# MCU_IO.net
KiCad netlist of a schematic drawn in Altium Designer
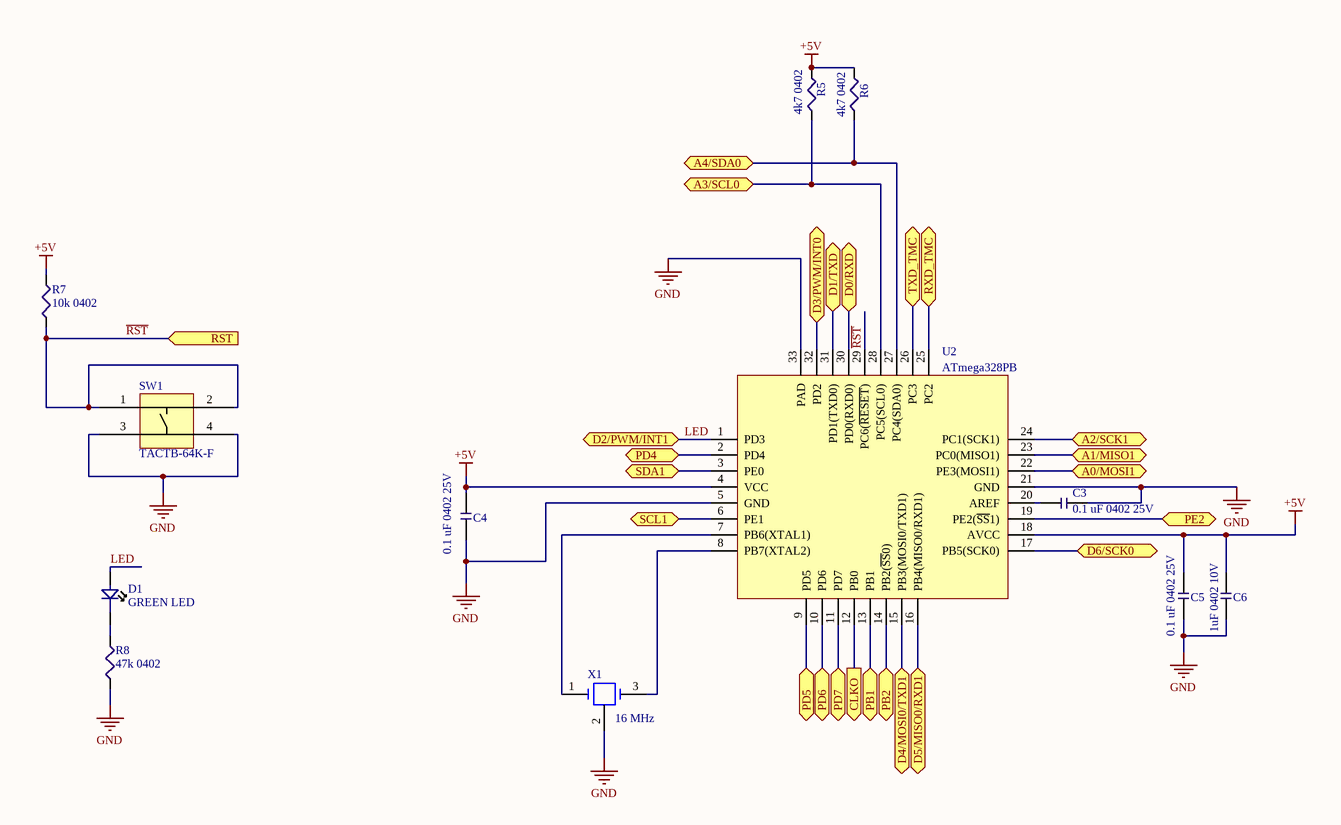
[diagram p0: MCU+IO.SchDoc]

(export (version "E")
  (design (tool "Eeschema 10.0.6"))
  (components
    (comp (ref "C3")
      (value "0.1 uF 0402 25V")
      (footprint "CAP_0402")
      (description "0.1UF 25V 10% X5R 0402")
      (fields (field (name "TOLERANCE") "10%") (field (name "VOLTAGE") "25V"))
      (libsource (lib "ON Development Vault") (part "Capacitor"))
    )
    (comp (ref "C4")
      (value "0.1 uF 0402 25V")
      (footprint "CAP_0402")
      (description "0.1UF 25V 10% X5R 0402")
      (fields (field (name "TOLERANCE") "10%") (field (name "VOLTAGE") "25V"))
      (libsource (lib "ON Development Vault") (part "Capacitor"))
    )
    (comp (ref "C5")
      (value "0.1 uF 0402 25V")
      (footprint "CAP_0402")
      (description "0.1UF 25V 10% X5R 0402")
      (fields (field (name "TOLERANCE") "10%") (field (name "VOLTAGE") "25V"))
      (libsource (lib "ON Development Vault") (part "Capacitor"))
    )
    (comp (ref "C6")
      (value "1uF 0402 10V")
      (footprint "CAP_0402")
      (description "1uF 0402 10V 10% X5R")
      (fields (field (name "TOLERANCE") "10 %") (field (name "VOLTAGE") "10 V"))
      (libsource (lib "ON Development Vault") (part "Capacitor"))
    )
    (comp (ref "D1")
      (value "GREEN LED")
      (footprint "0402 LED")
      (description "0402 SMD LED")
      (fields (field (name "MFG. PART NUMBER") "LTST-C281KGKT"))
      (libsource (lib "ON Development Vault") (part "LED"))
    )
    (comp (ref "R5")
      (value "4k7 0402")
      (footprint "RES_0402")
      (description "RES SMD 4.7K OHM 1% 1/16W 0402")
      (fields (field (name "POWER") "1/16W") (field (name "TOLERANCE") "1"))
      (libsource (lib "ON Development Vault") (part "Resistor"))
    )
    (comp (ref "R6")
      (value "4k7 0402")
      (footprint "RES_0402")
      (description "RES SMD 4.7K OHM 1% 1/16W 0402")
      (fields (field (name "POWER") "1/16W") (field (name "TOLERANCE") "1"))
      (libsource (lib "ON Development Vault") (part "Resistor"))
    )
    (comp (ref "R7")
      (value "10k 0402")
      (footprint "RES_0402")
      (description "RES SMD 10K OHM 1% 1/16W 0402")
      (fields (field (name "POWER") "1/16 W") (field (name "TOLERANCE") "1 %"))
      (libsource (lib "ON Development Vault") (part "Resistor"))
    )
    (comp (ref "R8")
      (value "47k 0402")
      (footprint "RES_0402")
      (description "RES SMD 47K OHM 1% 1/16W 0402")
      (fields (field (name "POWER") "1/16W") (field (name "TOLERANCE") "1%"))
      (libsource (lib "ON Development Vault") (part "Resistor"))
    )
    (comp (ref "SW1")
      (value "TACTB-64K-F")
      (footprint "TACTB-64K-F")
      (description "Microswitch TACT; SPST-NO; Positions:2; 0.05A/12VDC;")
      (libsource (lib "ON Development Vault") (part "CMP-013-0002-1"))
    )
    (comp (ref "U2")
      (value "ATmega328PB")
      (footprint "QFN50P500X500X90_HS-33N")
      (description "IC MCU 8BIT 32KB FLASH 32TQFP")
      (libsource (lib "ON Development Vault") (part "ATmega328PB"))
    )
    (comp (ref "X1")
      (value "16 MHz")
      (footprint "CSTCE16XTAL")
      (description "CER RES 16.0000MHZ 15PF SMD")
      (fields (field (name "MFG. PART NUMBER") "CSTCE16M0V53-R0"))
      (libsource (lib "ON Development Vault") (part "Xtal 3-pin"))
    )
  )
  (nets
    (net (code "1") (name "+5V") (class "Default")
      (node (ref "C4") (pin "1") (pinfunction "1_1") (pintype "passive"))
      (node (ref "C5") (pin "2") (pinfunction "2_2") (pintype "passive"))
      (node (ref "C6") (pin "2") (pinfunction "2_2") (pintype "passive"))
      (node (ref "R5") (pin "2") (pinfunction "2_2") (pintype "passive"))
      (node (ref "R6") (pin "2") (pinfunction "2_2") (pintype "passive"))
      (node (ref "R7") (pin "2") (pinfunction "2_2") (pintype "passive"))
      (node (ref "U2") (pin "18") (pinfunction "AVCC_18") (pintype "passive"))
      (node (ref "U2") (pin "4") (pinfunction "VCC_4") (pintype "passive"))
    )
    (net (code "2") (name "/A0{slash}MOSI1") (class "Default")
      (node (ref "U2") (pin "22") (pinfunction "PE3(MOSI1)_22") (pintype "passive"))
    )
    (net (code "3") (name "/A1{slash}MISO1") (class "Default")
      (node (ref "U2") (pin "23") (pinfunction "PC0(MISO1)_23") (pintype "passive"))
    )
    (net (code "4") (name "/A2{slash}SCK1") (class "Default")
      (node (ref "U2") (pin "24") (pinfunction "PC1(SCK1)_24") (pintype "passive"))
    )
    (net (code "5") (name "/A3{slash}SCL0") (class "Default")
      (node (ref "R5") (pin "1") (pinfunction "1_1") (pintype "passive"))
      (node (ref "U2") (pin "28") (pinfunction "PC5(SCL0)_28") (pintype "passive"))
    )
    (net (code "6") (name "/A4{slash}SDA0") (class "Default")
      (node (ref "R6") (pin "1") (pinfunction "1_1") (pintype "passive"))
      (node (ref "U2") (pin "27") (pinfunction "PC4(SDA0)_27") (pintype "passive"))
    )
    (net (code "7") (name "/CLKO") (class "Default")
      (node (ref "U2") (pin "12") (pinfunction "PB0_12") (pintype "passive"))
    )
    (net (code "8") (name "/D0{slash}RXD") (class "Default")
      (node (ref "U2") (pin "30") (pinfunction "PD0(RXD0)_30") (pintype "passive"))
    )
    (net (code "9") (name "/D1{slash}TXD") (class "Default")
      (node (ref "U2") (pin "31") (pinfunction "PD1(TXD0)_31") (pintype "passive"))
    )
    (net (code "10") (name "/D3{slash}PWM{slash}INT0") (class "Default")
      (node (ref "U2") (pin "32") (pinfunction "PD2_32") (pintype "passive"))
    )
    (net (code "11") (name "/D4{slash}MOSI0{slash}TXD1") (class "Default")
      (node (ref "U2") (pin "15") (pinfunction "PB3(MOSI0/TXD1)_15") (pintype "passive"))
    )
    (net (code "12") (name "/D5{slash}MISO0{slash}RXD1") (class "Default")
      (node (ref "U2") (pin "16") (pinfunction "PB4(MISO0/RXD1)_16") (pintype "passive"))
    )
    (net (code "13") (name "/D6{slash}SCK0") (class "Default")
      (node (ref "U2") (pin "17") (pinfunction "PB5(SCK0)_17") (pintype "passive"))
    )
    (net (code "14") (name "/LED") (class "Default")
      (node (ref "D1") (pin "1") (pinfunction "1_1") (pintype "passive"))
      (node (ref "U2") (pin "1") (pinfunction "PD3_1") (pintype "passive"))
    )
    (net (code "15") (name "/PB1") (class "Default")
      (node (ref "U2") (pin "13") (pinfunction "PB1_13") (pintype "passive"))
    )
    (net (code "16") (name "/PB2") (class "Default")
      (node (ref "U2") (pin "14") (pinfunction "PB2(~{SS}0)_14") (pintype "passive"))
    )
    (net (code "17") (name "/PD4") (class "Default")
      (node (ref "U2") (pin "2") (pinfunction "PD4_2") (pintype "passive"))
    )
    (net (code "18") (name "/PD5") (class "Default")
      (node (ref "U2") (pin "9") (pinfunction "PD5_9") (pintype "passive"))
    )
    (net (code "19") (name "/PD6") (class "Default")
      (node (ref "U2") (pin "10") (pinfunction "PD6_10") (pintype "passive"))
    )
    (net (code "20") (name "/PD7") (class "Default")
      (node (ref "U2") (pin "11") (pinfunction "PD7_11") (pintype "passive"))
    )
    (net (code "21") (name "/PE2") (class "Default")
      (node (ref "U2") (pin "19") (pinfunction "PE2(~{SS}1)_19") (pintype "passive"))
    )
    (net (code "22") (name "/RXD_TMC") (class "Default")
      (node (ref "U2") (pin "25") (pinfunction "PC2_25") (pintype "passive"))
    )
    (net (code "23") (name "/SCL1") (class "Default")
      (node (ref "U2") (pin "6") (pinfunction "PE1_6") (pintype "passive"))
    )
    (net (code "24") (name "/SDA1") (class "Default")
      (node (ref "U2") (pin "3") (pinfunction "PE0_3") (pintype "passive"))
    )
    (net (code "25") (name "/TXD_TMC") (class "Default")
      (node (ref "U2") (pin "26") (pinfunction "PC3_26") (pintype "passive"))
    )
    (net (code "26") (name "/~{RST}") (class "Default")
      (node (ref "R7") (pin "1") (pinfunction "1_1") (pintype "passive"))
      (node (ref "SW1") (pin "1") (pinfunction "1_1") (pintype "passive"))
      (node (ref "SW1") (pin "2") (pinfunction "2_2") (pintype "passive"))
      (node (ref "U2") (pin "29") (pinfunction "PC6(~{RESET})_29") (pintype "passive"))
    )
    (net (code "27") (name "GND") (class "Default")
      (node (ref "C3") (pin "1") (pinfunction "1_1") (pintype "passive"))
      (node (ref "C4") (pin "2") (pinfunction "2_2") (pintype "passive"))
      (node (ref "C5") (pin "1") (pinfunction "1_1") (pintype "passive"))
      (node (ref "C6") (pin "1") (pinfunction "1_1") (pintype "passive"))
      (node (ref "R8") (pin "1") (pinfunction "1_1") (pintype "passive"))
      (node (ref "SW1") (pin "3") (pinfunction "3_3") (pintype "passive"))
      (node (ref "SW1") (pin "4") (pinfunction "4_4") (pintype "passive"))
      (node (ref "U2") (pin "21") (pinfunction "GND_21") (pintype "passive"))
      (node (ref "U2") (pin "33") (pinfunction "PAD_33") (pintype "passive"))
      (node (ref "U2") (pin "5") (pinfunction "GND_5") (pintype "passive"))
      (node (ref "X1") (pin "2") (pinfunction "GND_2") (pintype "passive"))
    )
    (net (code "28") (name "Net-(D1-Pad2)") (class "Default")
      (node (ref "D1") (pin "2") (pinfunction "2_2") (pintype "passive"))
      (node (ref "R8") (pin "2") (pinfunction "2_2") (pintype "passive"))
    )
    (net (code "29") (name "Net-(U2-AREF)") (class "Default")
      (node (ref "C3") (pin "2") (pinfunction "2_2") (pintype "passive"))
      (node (ref "U2") (pin "20") (pinfunction "AREF_20") (pintype "passive"))
    )
    (net (code "30") (name "Net-(U2-PB6(XTAL1))") (class "Default")
      (node (ref "U2") (pin "7") (pinfunction "PB6(XTAL1)_7") (pintype "passive"))
      (node (ref "X1") (pin "1") (pinfunction "OSC1_1") (pintype "passive"))
    )
    (net (code "31") (name "Net-(U2-PB7(XTAL2))") (class "Default")
      (node (ref "U2") (pin "8") (pinfunction "PB7(XTAL2)_8") (pintype "passive"))
      (node (ref "X1") (pin "3") (pinfunction "OSC2_3") (pintype "passive"))
    )
  )
)
